# Arctos_65_V0.net
KiCad netlist of a schematic drawn in EAGLE
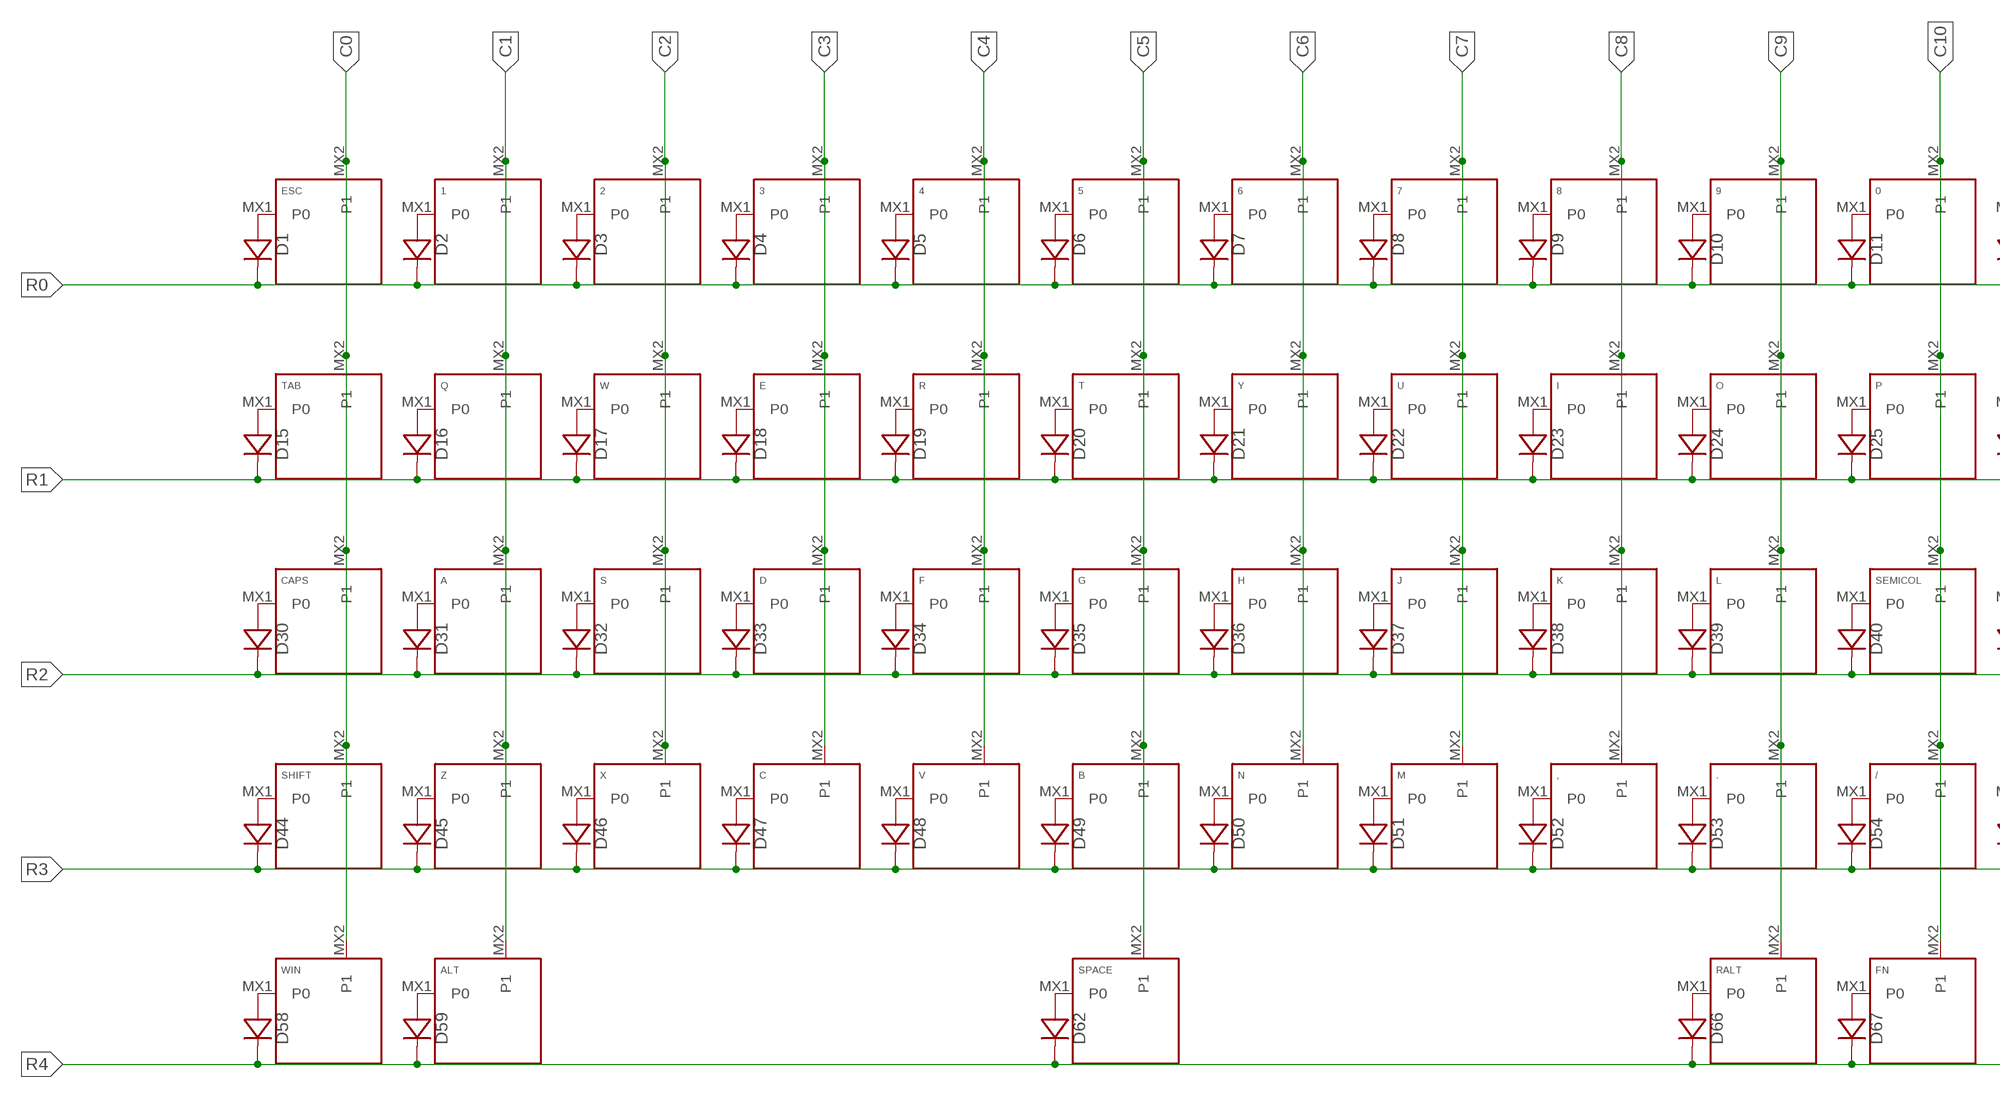
[diagram p0: schematic, sheet 1, part 1 of 2]
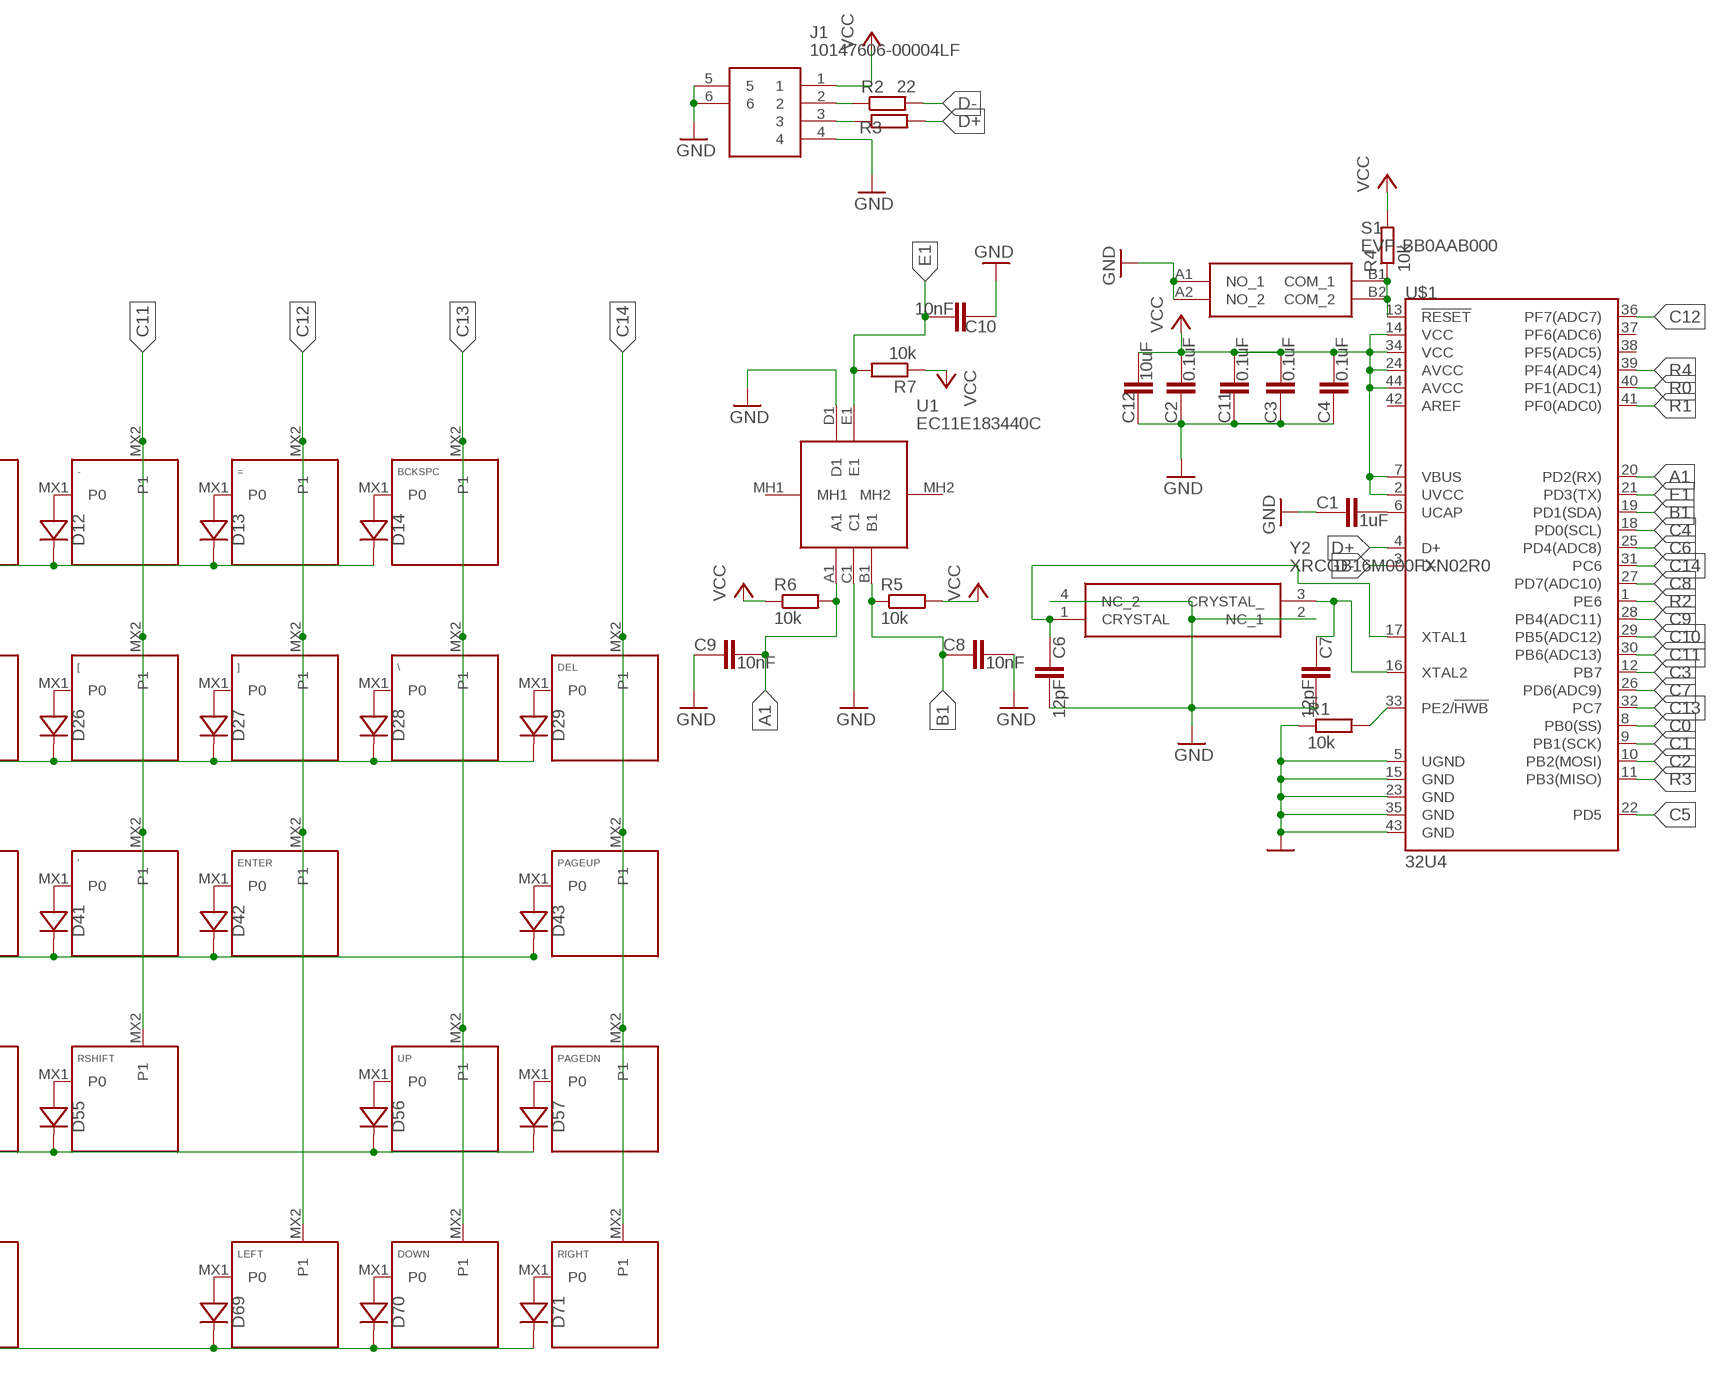
[diagram p1: schematic, sheet 1, part 2 of 2]

(export (version "E")
  (design (tool "Eeschema 10.0.6"))
  (components
    (comp (ref "'")
      (value "KEYSWITCH-PLAIN-MXHSPCB-1U")
      (footprint "eagle-import:MXHSPCB-1U")
      (libsource (lib "eagle-import") (part "KEYSWITCH-PLAIN-MXHSPCB-1U"))
    )
    (comp (ref ",")
      (value "KEYSWITCH-PLAIN-MXHSPCB-1U")
      (footprint "eagle-import:MXHSPCB-1U")
      (libsource (lib "eagle-import") (part "KEYSWITCH-PLAIN-MXHSPCB-1U"))
    )
    (comp (ref "-")
      (value "KEYSWITCH-PLAIN-MXHSPCB-1U")
      (footprint "eagle-import:MXHSPCB-1U")
      (libsource (lib "eagle-import") (part "KEYSWITCH-PLAIN-MXHSPCB-1U"))
    )
    (comp (ref ".")
      (value "KEYSWITCH-PLAIN-MXHSPCB-1U")
      (footprint "eagle-import:MXHSPCB-1U")
      (libsource (lib "eagle-import") (part "KEYSWITCH-PLAIN-MXHSPCB-1U"))
    )
    (comp (ref "/")
      (value "KEYSWITCH-PLAIN-MXHSPCB-1U")
      (footprint "eagle-import:MXHSPCB-1U")
      (libsource (lib "eagle-import") (part "KEYSWITCH-PLAIN-MXHSPCB-1U"))
    )
    (comp (ref "0")
      (value "KEYSWITCH-PLAIN-MXHSPCB-1U")
      (footprint "eagle-import:MXHSPCB-1U")
      (libsource (lib "eagle-import") (part "KEYSWITCH-PLAIN-MXHSPCB-1U"))
    )
    (comp (ref "1")
      (value "KEYSWITCH-PLAIN-MXHSPCB-1U")
      (footprint "eagle-import:MXHSPCB-1U")
      (libsource (lib "eagle-import") (part "KEYSWITCH-PLAIN-MXHSPCB-1U"))
    )
    (comp (ref "2")
      (value "KEYSWITCH-PLAIN-MXHSPCB-1U")
      (footprint "eagle-import:MXHSPCB-1U")
      (libsource (lib "eagle-import") (part "KEYSWITCH-PLAIN-MXHSPCB-1U"))
    )
    (comp (ref "3")
      (value "KEYSWITCH-PLAIN-MXHSPCB-1U")
      (footprint "eagle-import:MXHSPCB-1U")
      (libsource (lib "eagle-import") (part "KEYSWITCH-PLAIN-MXHSPCB-1U"))
    )
    (comp (ref "4")
      (value "KEYSWITCH-PLAIN-MXHSPCB-1U")
      (footprint "eagle-import:MXHSPCB-1U")
      (libsource (lib "eagle-import") (part "KEYSWITCH-PLAIN-MXHSPCB-1U"))
    )
    (comp (ref "5")
      (value "KEYSWITCH-PLAIN-MXHSPCB-1U")
      (footprint "eagle-import:MXHSPCB-1U")
      (libsource (lib "eagle-import") (part "KEYSWITCH-PLAIN-MXHSPCB-1U"))
    )
    (comp (ref "6")
      (value "KEYSWITCH-PLAIN-MXHSPCB-1U")
      (footprint "eagle-import:MXHSPCB-1U")
      (libsource (lib "eagle-import") (part "KEYSWITCH-PLAIN-MXHSPCB-1U"))
    )
    (comp (ref "7")
      (value "KEYSWITCH-PLAIN-MXHSPCB-1U")
      (footprint "eagle-import:MXHSPCB-1U")
      (libsource (lib "eagle-import") (part "KEYSWITCH-PLAIN-MXHSPCB-1U"))
    )
    (comp (ref "8")
      (value "KEYSWITCH-PLAIN-MXHSPCB-1U")
      (footprint "eagle-import:MXHSPCB-1U")
      (libsource (lib "eagle-import") (part "KEYSWITCH-PLAIN-MXHSPCB-1U"))
    )
    (comp (ref "9")
      (value "KEYSWITCH-PLAIN-MXHSPCB-1U")
      (footprint "eagle-import:MXHSPCB-1U")
      (libsource (lib "eagle-import") (part "KEYSWITCH-PLAIN-MXHSPCB-1U"))
    )
    (comp (ref "=")
      (value "KEYSWITCH-PLAIN-MXHSPCB-1U")
      (footprint "eagle-import:MXHSPCB-1U")
      (libsource (lib "eagle-import") (part "KEYSWITCH-PLAIN-MXHSPCB-1U"))
    )
    (comp (ref "A")
      (value "KEYSWITCH-PLAIN-MXHSPCB-1U")
      (footprint "eagle-import:MXHSPCB-1U")
      (libsource (lib "eagle-import") (part "KEYSWITCH-PLAIN-MXHSPCB-1U"))
    )
    (comp (ref "ALT")
      (value "KEYSWITCH-PLAIN-MXHSPCB-1U")
      (footprint "eagle-import:MXHSPCB-1U")
      (libsource (lib "eagle-import") (part "KEYSWITCH-PLAIN-MXHSPCB-1U"))
    )
    (comp (ref "B")
      (value "KEYSWITCH-PLAIN-MXHSPCB-1U")
      (footprint "eagle-import:MXHSPCB-1U")
      (libsource (lib "eagle-import") (part "KEYSWITCH-PLAIN-MXHSPCB-1U"))
    )
    (comp (ref "BCKSPC")
      (value "KEYSWITCH-PLAIN-MXHSPCB-2U")
      (footprint "eagle-import:MXHSPCB-2U")
      (libsource (lib "eagle-import") (part "KEYSWITCH-PLAIN-MXHSPCB-2U"))
    )
    (comp (ref "C")
      (value "KEYSWITCH-PLAIN-MXHSPCB-1U")
      (footprint "eagle-import:MXHSPCB-1U")
      (libsource (lib "eagle-import") (part "KEYSWITCH-PLAIN-MXHSPCB-1U"))
    )
    (comp (ref "C1")
      (value "1uF")
      (footprint "eagle-import:C0603")
      (libsource (lib "eagle-import") (part "CAPACITOR-0603"))
    )
    (comp (ref "C2")
      (value "0.1uF")
      (footprint "eagle-import:C0603")
      (libsource (lib "eagle-import") (part "CAPACITOR-0603"))
    )
    (comp (ref "C3")
      (value "0.1uF")
      (footprint "eagle-import:C0603")
      (libsource (lib "eagle-import") (part "CAPACITOR-0603"))
    )
    (comp (ref "C4")
      (value "0.1uF")
      (footprint "eagle-import:C0603")
      (libsource (lib "eagle-import") (part "CAPACITOR-0603"))
    )
    (comp (ref "C6")
      (value "12pF")
      (footprint "eagle-import:C0603")
      (libsource (lib "eagle-import") (part "CAPACITOR-0603"))
    )
    (comp (ref "C7")
      (value "12pF")
      (footprint "eagle-import:C0603")
      (libsource (lib "eagle-import") (part "CAPACITOR-0603"))
    )
    (comp (ref "C8")
      (value "10nF")
      (footprint "eagle-import:C0603")
      (libsource (lib "eagle-import") (part "CAPACITOR-0603"))
    )
    (comp (ref "C9")
      (value "10nF")
      (footprint "eagle-import:C0603")
      (libsource (lib "eagle-import") (part "CAPACITOR-0603"))
    )
    (comp (ref "C10")
      (value "10nF")
      (footprint "eagle-import:C0603")
      (libsource (lib "eagle-import") (part "CAPACITOR-0603"))
    )
    (comp (ref "C11")
      (value "0.1uF")
      (footprint "eagle-import:C0603")
      (libsource (lib "eagle-import") (part "CAPACITOR-0603"))
    )
    (comp (ref "C12")
      (value "10uF")
      (footprint "eagle-import:C0603")
      (libsource (lib "eagle-import") (part "CAPACITOR-0603"))
    )
    (comp (ref "CAPS")
      (value "KEYSWITCH-PLAIN-MXHSPCB-1U")
      (footprint "eagle-import:MXHSPCB-1U")
      (libsource (lib "eagle-import") (part "KEYSWITCH-PLAIN-MXHSPCB-1U"))
    )
    (comp (ref "D")
      (value "KEYSWITCH-PLAIN-MXHSPCB-1U")
      (footprint "eagle-import:MXHSPCB-1U")
      (libsource (lib "eagle-import") (part "KEYSWITCH-PLAIN-MXHSPCB-1U"))
    )
    (comp (ref "D1")
      (value "DIODE-SOD-123")
      (footprint "eagle-import:SOD-123")
      (libsource (lib "eagle-import") (part "DIODE-SOD-123"))
    )
    (comp (ref "D2")
      (value "DIODE-SOD-123")
      (footprint "eagle-import:SOD-123")
      (libsource (lib "eagle-import") (part "DIODE-SOD-123"))
    )
    (comp (ref "D3")
      (value "DIODE-SOD-123")
      (footprint "eagle-import:SOD-123")
      (libsource (lib "eagle-import") (part "DIODE-SOD-123"))
    )
    (comp (ref "D4")
      (value "DIODE-SOD-123")
      (footprint "eagle-import:SOD-123")
      (libsource (lib "eagle-import") (part "DIODE-SOD-123"))
    )
    (comp (ref "D5")
      (value "DIODE-SOD-123")
      (footprint "eagle-import:SOD-123")
      (libsource (lib "eagle-import") (part "DIODE-SOD-123"))
    )
    (comp (ref "D6")
      (value "DIODE-SOD-123")
      (footprint "eagle-import:SOD-123")
      (libsource (lib "eagle-import") (part "DIODE-SOD-123"))
    )
    (comp (ref "D7")
      (value "DIODE-SOD-123")
      (footprint "eagle-import:SOD-123")
      (libsource (lib "eagle-import") (part "DIODE-SOD-123"))
    )
    (comp (ref "D8")
      (value "DIODE-SOD-123")
      (footprint "eagle-import:SOD-123")
      (libsource (lib "eagle-import") (part "DIODE-SOD-123"))
    )
    (comp (ref "D9")
      (value "DIODE-SOD-123")
      (footprint "eagle-import:SOD-123")
      (libsource (lib "eagle-import") (part "DIODE-SOD-123"))
    )
    (comp (ref "D10")
      (value "DIODE-SOD-123")
      (footprint "eagle-import:SOD-123")
      (libsource (lib "eagle-import") (part "DIODE-SOD-123"))
    )
    (comp (ref "D11")
      (value "DIODE-SOD-123")
      (footprint "eagle-import:SOD-123")
      (libsource (lib "eagle-import") (part "DIODE-SOD-123"))
    )
    (comp (ref "D12")
      (value "DIODE-SOD-123")
      (footprint "eagle-import:SOD-123")
      (libsource (lib "eagle-import") (part "DIODE-SOD-123"))
    )
    (comp (ref "D13")
      (value "DIODE-SOD-123")
      (footprint "eagle-import:SOD-123")
      (libsource (lib "eagle-import") (part "DIODE-SOD-123"))
    )
    (comp (ref "D14")
      (value "DIODE-SOD-123")
      (footprint "eagle-import:SOD-123")
      (libsource (lib "eagle-import") (part "DIODE-SOD-123"))
    )
    (comp (ref "D15")
      (value "DIODE-SOD-123")
      (footprint "eagle-import:SOD-123")
      (libsource (lib "eagle-import") (part "DIODE-SOD-123"))
    )
    (comp (ref "D16")
      (value "DIODE-SOD-123")
      (footprint "eagle-import:SOD-123")
      (libsource (lib "eagle-import") (part "DIODE-SOD-123"))
    )
    (comp (ref "D17")
      (value "DIODE-SOD-123")
      (footprint "eagle-import:SOD-123")
      (libsource (lib "eagle-import") (part "DIODE-SOD-123"))
    )
    (comp (ref "D18")
      (value "DIODE-SOD-123")
      (footprint "eagle-import:SOD-123")
      (libsource (lib "eagle-import") (part "DIODE-SOD-123"))
    )
    (comp (ref "D19")
      (value "DIODE-SOD-123")
      (footprint "eagle-import:SOD-123")
      (libsource (lib "eagle-import") (part "DIODE-SOD-123"))
    )
    (comp (ref "D20")
      (value "DIODE-SOD-123")
      (footprint "eagle-import:SOD-123")
      (libsource (lib "eagle-import") (part "DIODE-SOD-123"))
    )
    (comp (ref "D21")
      (value "DIODE-SOD-123")
      (footprint "eagle-import:SOD-123")
      (libsource (lib "eagle-import") (part "DIODE-SOD-123"))
    )
    (comp (ref "D22")
      (value "DIODE-SOD-123")
      (footprint "eagle-import:SOD-123")
      (libsource (lib "eagle-import") (part "DIODE-SOD-123"))
    )
    (comp (ref "D23")
      (value "DIODE-SOD-123")
      (footprint "eagle-import:SOD-123")
      (libsource (lib "eagle-import") (part "DIODE-SOD-123"))
    )
    (comp (ref "D24")
      (value "DIODE-SOD-123")
      (footprint "eagle-import:SOD-123")
      (libsource (lib "eagle-import") (part "DIODE-SOD-123"))
    )
    (comp (ref "D25")
      (value "DIODE-SOD-123")
      (footprint "eagle-import:SOD-123")
      (libsource (lib "eagle-import") (part "DIODE-SOD-123"))
    )
    (comp (ref "D26")
      (value "DIODE-SOD-123")
      (footprint "eagle-import:SOD-123")
      (libsource (lib "eagle-import") (part "DIODE-SOD-123"))
    )
    (comp (ref "D27")
      (value "DIODE-SOD-123")
      (footprint "eagle-import:SOD-123")
      (libsource (lib "eagle-import") (part "DIODE-SOD-123"))
    )
    (comp (ref "D28")
      (value "DIODE-SOD-123")
      (footprint "eagle-import:SOD-123")
      (libsource (lib "eagle-import") (part "DIODE-SOD-123"))
    )
    (comp (ref "D29")
      (value "DIODE-SOD-123")
      (footprint "eagle-import:SOD-123")
      (libsource (lib "eagle-import") (part "DIODE-SOD-123"))
    )
    (comp (ref "D30")
      (value "DIODE-SOD-123")
      (footprint "eagle-import:SOD-123")
      (libsource (lib "eagle-import") (part "DIODE-SOD-123"))
    )
    (comp (ref "D31")
      (value "DIODE-SOD-123")
      (footprint "eagle-import:SOD-123")
      (libsource (lib "eagle-import") (part "DIODE-SOD-123"))
    )
    (comp (ref "D32")
      (value "DIODE-SOD-123")
      (footprint "eagle-import:SOD-123")
      (libsource (lib "eagle-import") (part "DIODE-SOD-123"))
    )
    (comp (ref "D33")
      (value "DIODE-SOD-123")
      (footprint "eagle-import:SOD-123")
      (libsource (lib "eagle-import") (part "DIODE-SOD-123"))
    )
    (comp (ref "D34")
      (value "DIODE-SOD-123")
      (footprint "eagle-import:SOD-123")
      (libsource (lib "eagle-import") (part "DIODE-SOD-123"))
    )
    (comp (ref "D35")
      (value "DIODE-SOD-123")
      (footprint "eagle-import:SOD-123")
      (libsource (lib "eagle-import") (part "DIODE-SOD-123"))
    )
    (comp (ref "D36")
      (value "DIODE-SOD-123")
      (footprint "eagle-import:SOD-123")
      (libsource (lib "eagle-import") (part "DIODE-SOD-123"))
    )
    (comp (ref "D37")
      (value "DIODE-SOD-123")
      (footprint "eagle-import:SOD-123")
      (libsource (lib "eagle-import") (part "DIODE-SOD-123"))
    )
    (comp (ref "D38")
      (value "DIODE-SOD-123")
      (footprint "eagle-import:SOD-123")
      (libsource (lib "eagle-import") (part "DIODE-SOD-123"))
    )
    (comp (ref "D39")
      (value "DIODE-SOD-123")
      (footprint "eagle-import:SOD-123")
      (libsource (lib "eagle-import") (part "DIODE-SOD-123"))
    )
    (comp (ref "D40")
      (value "DIODE-SOD-123")
      (footprint "eagle-import:SOD-123")
      (libsource (lib "eagle-import") (part "DIODE-SOD-123"))
    )
    (comp (ref "D41")
      (value "DIODE-SOD-123")
      (footprint "eagle-import:SOD-123")
      (libsource (lib "eagle-import") (part "DIODE-SOD-123"))
    )
    (comp (ref "D42")
      (value "DIODE-SOD-123")
      (footprint "eagle-import:SOD-123")
      (libsource (lib "eagle-import") (part "DIODE-SOD-123"))
    )
    (comp (ref "D43")
      (value "DIODE-SOD-123")
      (footprint "eagle-import:SOD-123")
      (libsource (lib "eagle-import") (part "DIODE-SOD-123"))
    )
    (comp (ref "D44")
      (value "DIODE-SOD-123")
      (footprint "eagle-import:SOD-123")
      (libsource (lib "eagle-import") (part "DIODE-SOD-123"))
    )
    (comp (ref "D45")
      (value "DIODE-SOD-123")
      (footprint "eagle-import:SOD-123")
      (libsource (lib "eagle-import") (part "DIODE-SOD-123"))
    )
    (comp (ref "D46")
      (value "DIODE-SOD-123")
      (footprint "eagle-import:SOD-123")
      (libsource (lib "eagle-import") (part "DIODE-SOD-123"))
    )
    (comp (ref "D47")
      (value "DIODE-SOD-123")
      (footprint "eagle-import:SOD-123")
      (libsource (lib "eagle-import") (part "DIODE-SOD-123"))
    )
    (comp (ref "D48")
      (value "DIODE-SOD-123")
      (footprint "eagle-import:SOD-123")
      (libsource (lib "eagle-import") (part "DIODE-SOD-123"))
    )
    (comp (ref "D49")
      (value "DIODE-SOD-123")
      (footprint "eagle-import:SOD-123")
      (libsource (lib "eagle-import") (part "DIODE-SOD-123"))
    )
    (comp (ref "D50")
      (value "DIODE-SOD-123")
      (footprint "eagle-import:SOD-123")
      (libsource (lib "eagle-import") (part "DIODE-SOD-123"))
    )
    (comp (ref "D51")
      (value "DIODE-SOD-123")
      (footprint "eagle-import:SOD-123")
      (libsource (lib "eagle-import") (part "DIODE-SOD-123"))
    )
    (comp (ref "D52")
      (value "DIODE-SOD-123")
      (footprint "eagle-import:SOD-123")
      (libsource (lib "eagle-import") (part "DIODE-SOD-123"))
    )
    (comp (ref "D53")
      (value "DIODE-SOD-123")
      (footprint "eagle-import:SOD-123")
      (libsource (lib "eagle-import") (part "DIODE-SOD-123"))
    )
    (comp (ref "D54")
      (value "DIODE-SOD-123")
      (footprint "eagle-import:SOD-123")
      (libsource (lib "eagle-import") (part "DIODE-SOD-123"))
    )
    (comp (ref "D55")
      (value "DIODE-SOD-123")
      (footprint "eagle-import:SOD-123")
      (libsource (lib "eagle-import") (part "DIODE-SOD-123"))
    )
    (comp (ref "D56")
      (value "DIODE-SOD-123")
      (footprint "eagle-import:SOD-123")
      (libsource (lib "eagle-import") (part "DIODE-SOD-123"))
    )
    (comp (ref "D57")
      (value "DIODE-SOD-123")
      (footprint "eagle-import:SOD-123")
      (libsource (lib "eagle-import") (part "DIODE-SOD-123"))
    )
    (comp (ref "D58")
      (value "DIODE-SOD-123")
      (footprint "eagle-import:SOD-123")
      (libsource (lib "eagle-import") (part "DIODE-SOD-123"))
    )
    (comp (ref "D59")
      (value "DIODE-SOD-123")
      (footprint "eagle-import:SOD-123")
      (libsource (lib "eagle-import") (part "DIODE-SOD-123"))
    )
    (comp (ref "D62")
      (value "DIODE-SOD-123")
      (footprint "eagle-import:SOD-123")
      (libsource (lib "eagle-import") (part "DIODE-SOD-123"))
    )
    (comp (ref "D66")
      (value "DIODE-SOD-123")
      (footprint "eagle-import:SOD-123")
      (libsource (lib "eagle-import") (part "DIODE-SOD-123"))
    )
    (comp (ref "D67")
      (value "DIODE-SOD-123")
      (footprint "eagle-import:SOD-123")
      (libsource (lib "eagle-import") (part "DIODE-SOD-123"))
    )
    (comp (ref "D69")
      (value "DIODE-SOD-123")
      (footprint "eagle-import:SOD-123")
      (libsource (lib "eagle-import") (part "DIODE-SOD-123"))
    )
    (comp (ref "D70")
      (value "DIODE-SOD-123")
      (footprint "eagle-import:SOD-123")
      (libsource (lib "eagle-import") (part "DIODE-SOD-123"))
    )
    (comp (ref "D71")
      (value "DIODE-SOD-123")
      (footprint "eagle-import:SOD-123")
      (libsource (lib "eagle-import") (part "DIODE-SOD-123"))
    )
    (comp (ref "DEL")
      (value "KEYSWITCH-PLAIN-MXHSPCB-1U")
      (footprint "eagle-import:MXHSPCB-1U")
      (libsource (lib "eagle-import") (part "KEYSWITCH-PLAIN-MXHSPCB-1U"))
    )
    (comp (ref "DOWN")
      (value "KEYSWITCH-PLAIN-MXHSPCB-1U")
      (footprint "eagle-import:MXHSPCB-1U")
      (libsource (lib "eagle-import") (part "KEYSWITCH-PLAIN-MXHSPCB-1U"))
    )
    (comp (ref "E")
      (value "KEYSWITCH-PLAIN-MXHSPCB-1U")
      (footprint "eagle-import:MXHSPCB-1U")
      (libsource (lib "eagle-import") (part "KEYSWITCH-PLAIN-MXHSPCB-1U"))
    )
    (comp (ref "ENTER")
      (value "KEYSWITCH-PLAIN-MXHSPCB-2U")
      (footprint "eagle-import:MXHSPCB-2U")
      (libsource (lib "eagle-import") (part "KEYSWITCH-PLAIN-MXHSPCB-2U"))
    )
    (comp (ref "ESC")
      (value "KEYSWITCH-PLAIN-MXHSPCB-1U")
      (footprint "eagle-import:MXHSPCB-1U")
      (libsource (lib "eagle-import") (part "KEYSWITCH-PLAIN-MXHSPCB-1U"))
    )
    (comp (ref "F")
      (value "KEYSWITCH-PLAIN-MXHSPCB-1U")
      (footprint "eagle-import:MXHSPCB-1U")
      (libsource (lib "eagle-import") (part "KEYSWITCH-PLAIN-MXHSPCB-1U"))
    )
    (comp (ref "FN")
      (value "KEYSWITCH-PLAIN-MXHSPCB-1U")
      (footprint "eagle-import:MXHSPCB-1U")
      (libsource (lib "eagle-import") (part "KEYSWITCH-PLAIN-MXHSPCB-1U"))
    )
    (comp (ref "G")
      (value "KEYSWITCH-PLAIN-MXHSPCB-1U")
      (footprint "eagle-import:MXHSPCB-1U")
      (libsource (lib "eagle-import") (part "KEYSWITCH-PLAIN-MXHSPCB-1U"))
    )
    (comp (ref "H")
      (value "KEYSWITCH-PLAIN-MXHSPCB-1U")
      (footprint "eagle-import:MXHSPCB-1U")
      (libsource (lib "eagle-import") (part "KEYSWITCH-PLAIN-MXHSPCB-1U"))
    )
    (comp (ref "I")
      (value "KEYSWITCH-PLAIN-MXHSPCB-1U")
      (footprint "eagle-import:MXHSPCB-1U")
      (libsource (lib "eagle-import") (part "KEYSWITCH-PLAIN-MXHSPCB-1U"))
    )
    (comp (ref "J")
      (value "KEYSWITCH-PLAIN-MXHSPCB-1U")
      (footprint "eagle-import:MXHSPCB-1U")
      (libsource (lib "eagle-import") (part "KEYSWITCH-PLAIN-MXHSPCB-1U"))
    )
    (comp (ref "J1")
      (value "10147606-00004LF")
      (footprint "eagle-import:1014760600004LF")
      (fields (field (name "MOUSER_PART_NUMBER") "649-10147606-00004LF"))
      (libsource (lib "eagle-import") (part "10147606-00004LF"))
    )
    (comp (ref "K")
      (value "KEYSWITCH-PLAIN-MXHSPCB-1U")
      (footprint "eagle-import:MXHSPCB-1U")
      (libsource (lib "eagle-import") (part "KEYSWITCH-PLAIN-MXHSPCB-1U"))
    )
    (comp (ref "L")
      (value "KEYSWITCH-PLAIN-MXHSPCB-1U")
      (footprint "eagle-import:MXHSPCB-1U")
      (libsource (lib "eagle-import") (part "KEYSWITCH-PLAIN-MXHSPCB-1U"))
    )
    (comp (ref "LEFT")
      (value "KEYSWITCH-PLAIN-MXHSPCB-1U")
      (footprint "eagle-import:MXHSPCB-1U")
      (libsource (lib "eagle-import") (part "KEYSWITCH-PLAIN-MXHSPCB-1U"))
    )
    (comp (ref "M")
      (value "KEYSWITCH-PLAIN-MXHSPCB-1U")
      (footprint "eagle-import:MXHSPCB-1U")
      (libsource (lib "eagle-import") (part "KEYSWITCH-PLAIN-MXHSPCB-1U"))
    )
    (comp (ref "N")
      (value "KEYSWITCH-PLAIN-MXHSPCB-1U")
      (footprint "eagle-import:MXHSPCB-1U")
      (libsource (lib "eagle-import") (part "KEYSWITCH-PLAIN-MXHSPCB-1U"))
    )
    (comp (ref "O")
      (value "KEYSWITCH-PLAIN-MXHSPCB-1U")
      (footprint "eagle-import:MXHSPCB-1U")
      (libsource (lib "eagle-import") (part "KEYSWITCH-PLAIN-MXHSPCB-1U"))
    )
    (comp (ref "P")
      (value "KEYSWITCH-PLAIN-MXHSPCB-1U")
      (footprint "eagle-import:MXHSPCB-1U")
      (libsource (lib "eagle-import") (part "KEYSWITCH-PLAIN-MXHSPCB-1U"))
    )
    (comp (ref "PAGEDN")
      (value "KEYSWITCH-PLAIN-MXHSPCB-1U")
      (footprint "eagle-import:MXHSPCB-1U")
      (libsource (lib "eagle-import") (part "KEYSWITCH-PLAIN-MXHSPCB-1U"))
    )
    (comp (ref "PAGEUP")
      (value "KEYSWITCH-PLAIN-MXHSPCB-1U")
      (footprint "eagle-import:MXHSPCB-1U")
      (libsource (lib "eagle-import") (part "KEYSWITCH-PLAIN-MXHSPCB-1U"))
    )
    (comp (ref "Q")
      (value "KEYSWITCH-PLAIN-MXHSPCB-1U")
      (footprint "eagle-import:MXHSPCB-1U")
      (libsource (lib "eagle-import") (part "KEYSWITCH-PLAIN-MXHSPCB-1U"))
    )
    (comp (ref "R")
      (value "KEYSWITCH-PLAIN-MXHSPCB-1U")
      (footprint "eagle-import:MXHSPCB-1U")
      (libsource (lib "eagle-import") (part "KEYSWITCH-PLAIN-MXHSPCB-1U"))
    )
    (comp (ref "R1")
      (value "10k")
      (footprint "eagle-import:R0603")
      (libsource (lib "eagle-import") (part "RESISTOR-0603"))
    )
    (comp (ref "R2")
      (value "22")
      (footprint "eagle-import:R0603")
      (libsource (lib "eagle-import") (part "RESISTOR-0603"))
    )
    (comp (ref "R3")
      (value "22")
      (footprint "eagle-import:R0603")
      (libsource (lib "eagle-import") (part "RESISTOR-0603"))
    )
    (comp (ref "R4")
      (value "10k")
      (footprint "eagle-import:R0603")
      (libsource (lib "eagle-import") (part "RESISTOR-0603"))
    )
    (comp (ref "R5")
      (value "10k")
      (footprint "eagle-import:R0603")
      (libsource (lib "eagle-import") (part "RESISTOR-0603"))
    )
    (comp (ref "R6")
      (value "10k")
      (footprint "eagle-import:R0603")
      (libsource (lib "eagle-import") (part "RESISTOR-0603"))
    )
    (comp (ref "R7")
      (value "10k")
      (footprint "eagle-import:R0603")
      (libsource (lib "eagle-import") (part "RESISTOR-0603"))
    )
    (comp (ref "RALT")
      (value "KEYSWITCH-PLAIN-MXHSPCB-1U")
      (footprint "eagle-import:MXHSPCB-1U")
      (libsource (lib "eagle-import") (part "KEYSWITCH-PLAIN-MXHSPCB-1U"))
    )
    (comp (ref "RIGHT")
      (value "KEYSWITCH-PLAIN-MXHSPCB-1U")
      (footprint "eagle-import:MXHSPCB-1U")
      (libsource (lib "eagle-import") (part "KEYSWITCH-PLAIN-MXHSPCB-1U"))
    )
    (comp (ref "RSHIFT")
      (value "KEYSWITCH-PLAIN-MXHSPCB-1U")
      (footprint "eagle-import:MXHSPCB-1U")
      (libsource (lib "eagle-import") (part "KEYSWITCH-PLAIN-MXHSPCB-1U"))
    )
    (comp (ref "S")
      (value "KEYSWITCH-PLAIN-MXHSPCB-1U")
      (footprint "eagle-import:MXHSPCB-1U")
      (libsource (lib "eagle-import") (part "KEYSWITCH-PLAIN-MXHSPCB-1U"))
    )
    (comp (ref "S1")
      (value "EVP-BB0AAB000")
      (footprint "eagle-import:EVPBB0AAB000")
      (fields (field (name "MOUSER_PART_NUMBER") "667-EVP-BB0AAB000"))
      (libsource (lib "eagle-import") (part "EVP-BB0AAB000"))
    )
    (comp (ref "SEMICOL")
      (value "KEYSWITCH-PLAIN-MXHSPCB-1U")
      (footprint "eagle-import:MXHSPCB-1U")
      (libsource (lib "eagle-import") (part "KEYSWITCH-PLAIN-MXHSPCB-1U"))
    )
    (comp (ref "SHIFT")
      (value "KEYSWITCH-PLAIN-MXHSPCB-2U")
      (footprint "eagle-import:MXHSPCB-2U")
      (libsource (lib "eagle-import") (part "KEYSWITCH-PLAIN-MXHSPCB-2U"))
    )
    (comp (ref "SPACE")
      (value "KEYSWITCH-PLAIN-MXHSPCB-7U-FLIPPED")
      (footprint "eagle-import:MXHSPCB-7U-FLIPPED")
      (libsource (lib "eagle-import") (part "KEYSWITCH-PLAIN-MXHSPCB-7U-FLIPPED"))
    )
    (comp (ref "T")
      (value "KEYSWITCH-PLAIN-MXHSPCB-1U")
      (footprint "eagle-import:MXHSPCB-1U")
      (libsource (lib "eagle-import") (part "KEYSWITCH-PLAIN-MXHSPCB-1U"))
    )
    (comp (ref "TAB")
      (value "KEYSWITCH-PLAIN-MXHSPCB-1U")
      (footprint "eagle-import:MXHSPCB-1U")
      (libsource (lib "eagle-import") (part "KEYSWITCH-PLAIN-MXHSPCB-1U"))
    )
    (comp (ref "U")
      (value "KEYSWITCH-PLAIN-MXHSPCB-1U")
      (footprint "eagle-import:MXHSPCB-1U")
      (libsource (lib "eagle-import") (part "KEYSWITCH-PLAIN-MXHSPCB-1U"))
    )
    (comp (ref "U$1")
      (value "32U4")
      (footprint "eagle-import:TQFP44")
      (libsource (lib "eagle-import") (part "ATMEGA32U4TQFP-44"))
    )
    (comp (ref "U1")
      (value "EC11E183440C")
      (footprint "eagle-import:EC11E183440C")
      (fields (field (name "MOUSER_PART_NUMBER") "688-EC11E183440C"))
      (libsource (lib "eagle-import") (part "EC11E183440C"))
    )
    (comp (ref "UP")
      (value "KEYSWITCH-PLAIN-MXHSPCB-1U")
      (footprint "eagle-import:MXHSPCB-1U")
      (libsource (lib "eagle-import") (part "KEYSWITCH-PLAIN-MXHSPCB-1U"))
    )
    (comp (ref "V")
      (value "KEYSWITCH-PLAIN-MXHSPCB-1U")
      (footprint "eagle-import:MXHSPCB-1U")
      (libsource (lib "eagle-import") (part "KEYSWITCH-PLAIN-MXHSPCB-1U"))
    )
    (comp (ref "W")
      (value "KEYSWITCH-PLAIN-MXHSPCB-1U")
      (footprint "eagle-import:MXHSPCB-1U")
      (libsource (lib "eagle-import") (part "KEYSWITCH-PLAIN-MXHSPCB-1U"))
    )
    (comp (ref "WIN")
      (value "KEYSWITCH-PLAIN-MXHSPCB-1U")
      (footprint "eagle-import:MXHSPCB-1U")
      (libsource (lib "eagle-import") (part "KEYSWITCH-PLAIN-MXHSPCB-1U"))
    )
    (comp (ref "X")
      (value "KEYSWITCH-PLAIN-MXHSPCB-1U")
      (footprint "eagle-import:MXHSPCB-1U")
      (libsource (lib "eagle-import") (part "KEYSWITCH-PLAIN-MXHSPCB-1U"))
    )
    (comp (ref "Y")
      (value "KEYSWITCH-PLAIN-MXHSPCB-1U")
      (footprint "eagle-import:MXHSPCB-1U")
      (libsource (lib "eagle-import") (part "KEYSWITCH-PLAIN-MXHSPCB-1U"))
    )
    (comp (ref "Y2")
      (value "XRCGB16M000FXN02R0")
      (footprint "eagle-import:XRCGB16M000FXN02R0")
      (fields (field (name "MOUSER_PART_NUMBER") "81-XRCGB16M000FXN02R"))
      (libsource (lib "eagle-import") (part "XRCGB16M000FXN02R0"))
    )
    (comp (ref "Z")
      (value "KEYSWITCH-PLAIN-MXHSPCB-1U")
      (footprint "eagle-import:MXHSPCB-1U")
      (libsource (lib "eagle-import") (part "KEYSWITCH-PLAIN-MXHSPCB-1U"))
    )
    (comp (ref "[")
      (value "KEYSWITCH-PLAIN-MXHSPCB-1U")
      (footprint "eagle-import:MXHSPCB-1U")
      (libsource (lib "eagle-import") (part "KEYSWITCH-PLAIN-MXHSPCB-1U"))
    )
    (comp (ref "\\")
      (value "KEYSWITCH-PLAIN-MXHSPCB-1U")
      (footprint "eagle-import:MXHSPCB-1U")
      (libsource (lib "eagle-import") (part "KEYSWITCH-PLAIN-MXHSPCB-1U"))
    )
    (comp (ref "]")
      (value "KEYSWITCH-PLAIN-MXHSPCB-1U")
      (footprint "eagle-import:MXHSPCB-1U")
      (libsource (lib "eagle-import") (part "KEYSWITCH-PLAIN-MXHSPCB-1U"))
    )
  )
  (nets
    (net (code "1") (name "A1") (class "Default")
      (node (ref "C9") (pin "2") (pinfunction "2_2") (pintype "passive"))
      (node (ref "R6") (pin "2") (pinfunction "2_2") (pintype "passive"))
      (node (ref "U$1") (pin "20") (pinfunction "PD2(RX)_20") (pintype "bidirectional"))
      (node (ref "U1") (pin "A1") (pinfunction "A1_A1") (pintype "bidirectional"))
    )
    (net (code "2") (name "B1") (class "Default")
      (node (ref "C8") (pin "1") (pinfunction "1_1") (pintype "passive"))
      (node (ref "R5") (pin "1") (pinfunction "1_1") (pintype "passive"))
      (node (ref "U$1") (pin "19") (pinfunction "PD1(SDA)_19") (pintype "bidirectional"))
      (node (ref "U1") (pin "B1") (pinfunction "B1_B1") (pintype "bidirectional"))
    )
    (net (code "3") (name "C0") (class "Default")
      (node (ref "CAPS") (pin "MX2") (pinfunction "P1_MX2") (pintype "bidirectional"))
      (node (ref "ESC") (pin "MX2") (pinfunction "P1_MX2") (pintype "bidirectional"))
      (node (ref "SHIFT") (pin "MX2") (pinfunction "P1_MX2") (pintype "bidirectional"))
      (node (ref "TAB") (pin "MX2") (pinfunction "P1_MX2") (pintype "bidirectional"))
      (node (ref "U$1") (pin "8") (pinfunction "PB0(SS)_8") (pintype "bidirectional"))
      (node (ref "WIN") (pin "MX2") (pinfunction "P1_MX2") (pintype "bidirectional"))
    )
    (net (code "4") (name "C1") (class "Default")
      (node (ref "1") (pin "MX2") (pinfunction "P1_MX2") (pintype "bidirectional"))
      (node (ref "A") (pin "MX2") (pinfunction "P1_MX2") (pintype "bidirectional"))
      (node (ref "ALT") (pin "MX2") (pinfunction "P1_MX2") (pintype "bidirectional"))
      (node (ref "Q") (pin "MX2") (pinfunction "P1_MX2") (pintype "bidirectional"))
      (node (ref "U$1") (pin "9") (pinfunction "PB1(SCK)_9") (pintype "bidirectional"))
      (node (ref "Z") (pin "MX2") (pinfunction "P1_MX2") (pintype "bidirectional"))
    )
    (net (code "5") (name "C2") (class "Default")
      (node (ref "2") (pin "MX2") (pinfunction "P1_MX2") (pintype "bidirectional"))
      (node (ref "S") (pin "MX2") (pinfunction "P1_MX2") (pintype "bidirectional"))
      (node (ref "U$1") (pin "10") (pinfunction "PB2(MOSI)_10") (pintype "bidirectional"))
      (node (ref "W") (pin "MX2") (pinfunction "P1_MX2") (pintype "bidirectional"))
      (node (ref "X") (pin "MX2") (pinfunction "P1_MX2") (pintype "bidirectional"))
    )
    (net (code "6") (name "C3") (class "Default")
      (node (ref "3") (pin "MX2") (pinfunction "P1_MX2") (pintype "bidirectional"))
      (node (ref "C") (pin "MX2") (pinfunction "P1_MX2") (pintype "bidirectional"))
      (node (ref "D") (pin "MX2") (pinfunction "P1_MX2") (pintype "bidirectional"))
      (node (ref "E") (pin "MX2") (pinfunction "P1_MX2") (pintype "bidirectional"))
      (node (ref "U$1") (pin "12") (pinfunction "PB7_12") (pintype "bidirectional"))
    )
    (net (code "7") (name "C4") (class "Default")
      (node (ref "4") (pin "MX2") (pinfunction "P1_MX2") (pintype "bidirectional"))
      (node (ref "F") (pin "MX2") (pinfunction "P1_MX2") (pintype "bidirectional"))
      (node (ref "R") (pin "MX2") (pinfunction "P1_MX2") (pintype "bidirectional"))
      (node (ref "U$1") (pin "18") (pinfunction "PD0(SCL)_18") (pintype "bidirectional"))
      (node (ref "V") (pin "MX2") (pinfunction "P1_MX2") (pintype "bidirectional"))
    )
    (net (code "8") (name "C5") (class "Default")
      (node (ref "5") (pin "MX2") (pinfunction "P1_MX2") (pintype "bidirectional"))
      (node (ref "B") (pin "MX2") (pinfunction "P1_MX2") (pintype "bidirectional"))
      (node (ref "G") (pin "MX2") (pinfunction "P1_MX2") (pintype "bidirectional"))
      (node (ref "SPACE") (pin "MX2") (pinfunction "P1_MX2") (pintype "bidirectional"))
      (node (ref "T") (pin "MX2") (pinfunction "P1_MX2") (pintype "bidirectional"))
      (node (ref "U$1") (pin "22") (pinfunction "PD5_22") (pintype "bidirectional"))
    )
    (net (code "9") (name "C6") (class "Default")
      (node (ref "6") (pin "MX2") (pinfunction "P1_MX2") (pintype "bidirectional"))
      (node (ref "H") (pin "MX2") (pinfunction "P1_MX2") (pintype "bidirectional"))
      (node (ref "N") (pin "MX2") (pinfunction "P1_MX2") (pintype "bidirectional"))
      (node (ref "U$1") (pin "25") (pinfunction "PD4(ADC8)_25") (pintype "bidirectional"))
      (node (ref "Y") (pin "MX2") (pinfunction "P1_MX2") (pintype "bidirectional"))
    )
    (net (code "10") (name "C7") (class "Default")
      (node (ref "7") (pin "MX2") (pinfunction "P1_MX2") (pintype "bidirectional"))
      (node (ref "J") (pin "MX2") (pinfunction "P1_MX2") (pintype "bidirectional"))
      (node (ref "M") (pin "MX2") (pinfunction "P1_MX2") (pintype "bidirectional"))
      (node (ref "U") (pin "MX2") (pinfunction "P1_MX2") (pintype "bidirectional"))
      (node (ref "U$1") (pin "26") (pinfunction "PD6(ADC9)_26") (pintype "bidirectional"))
    )
    (net (code "11") (name "C8") (class "Default")
      (node (ref ",") (pin "MX2") (pinfunction "P1_MX2") (pintype "bidirectional"))
      (node (ref "8") (pin "MX2") (pinfunction "P1_MX2") (pintype "bidirectional"))
      (node (ref "I") (pin "MX2") (pinfunction "P1_MX2") (pintype "bidirectional"))
      (node (ref "K") (pin "MX2") (pinfunction "P1_MX2") (pintype "bidirectional"))
      (node (ref "U$1") (pin "27") (pinfunction "PD7(ADC10)_27") (pintype "bidirectional"))
    )
    (net (code "12") (name "C9") (class "Default")
      (node (ref ".") (pin "MX2") (pinfunction "P1_MX2") (pintype "bidirectional"))
      (node (ref "9") (pin "MX2") (pinfunction "P1_MX2") (pintype "bidirectional"))
      (node (ref "L") (pin "MX2") (pinfunction "P1_MX2") (pintype "bidirectional"))
      (node (ref "O") (pin "MX2") (pinfunction "P1_MX2") (pintype "bidirectional"))
      (node (ref "RALT") (pin "MX2") (pinfunction "P1_MX2") (pintype "bidirectional"))
      (node (ref "U$1") (pin "28") (pinfunction "PB4(ADC11)_28") (pintype "bidirectional"))
    )
    (net (code "13") (name "C10") (class "Default")
      (node (ref "/") (pin "MX2") (pinfunction "P1_MX2") (pintype "bidirectional"))
      (node (ref "0") (pin "MX2") (pinfunction "P1_MX2") (pintype "bidirectional"))
      (node (ref "FN") (pin "MX2") (pinfunction "P1_MX2") (pintype "bidirectional"))
      (node (ref "P") (pin "MX2") (pinfunction "P1_MX2") (pintype "bidirectional"))
      (node (ref "SEMICOL") (pin "MX2") (pinfunction "P1_MX2") (pintype "bidirectional"))
      (node (ref "U$1") (pin "29") (pinfunction "PB5(ADC12)_29") (pintype "bidirectional"))
    )
    (net (code "14") (name "C11") (class "Default")
      (node (ref "'") (pin "MX2") (pinfunction "P1_MX2") (pintype "bidirectional"))
      (node (ref "-") (pin "MX2") (pinfunction "P1_MX2") (pintype "bidirectional"))
      (node (ref "RSHIFT") (pin "MX2") (pinfunction "P1_MX2") (pintype "bidirectional"))
      (node (ref "U$1") (pin "30") (pinfunction "PB6(ADC13)_30") (pintype "bidirectional"))
      (node (ref "[") (pin "MX2") (pinfunction "P1_MX2") (pintype "bidirectional"))
    )
    (net (code "15") (name "C12") (class "Default")
      (node (ref "=") (pin "MX2") (pinfunction "P1_MX2") (pintype "bidirectional"))
      (node (ref "ENTER") (pin "MX2") (pinfunction "P1_MX2") (pintype "bidirectional"))
      (node (ref "LEFT") (pin "MX2") (pinfunction "P1_MX2") (pintype "bidirectional"))
      (node (ref "U$1") (pin "36") (pinfunction "PF7(ADC7)_36") (pintype "bidirectional"))
      (node (ref "]") (pin "MX2") (pinfunction "P1_MX2") (pintype "bidirectional"))
    )
    (net (code "16") (name "C13") (class "Default")
      (node (ref "BCKSPC") (pin "MX2") (pinfunction "P1_MX2") (pintype "bidirectional"))
      (node (ref "DOWN") (pin "MX2") (pinfunction "P1_MX2") (pintype "bidirectional"))
      (node (ref "U$1") (pin "32") (pinfunction "PC7_32") (pintype "bidirectional"))
      (node (ref "UP") (pin "MX2") (pinfunction "P1_MX2") (pintype "bidirectional"))
      (node (ref "\\") (pin "MX2") (pinfunction "P1_MX2") (pintype "bidirectional"))
    )
    (net (code "17") (name "C14") (class "Default")
      (node (ref "DEL") (pin "MX2") (pinfunction "P1_MX2") (pintype "bidirectional"))
      (node (ref "PAGEDN") (pin "MX2") (pinfunction "P1_MX2") (pintype "bidirectional"))
      (node (ref "PAGEUP") (pin "MX2") (pinfunction "P1_MX2") (pintype "bidirectional"))
      (node (ref "RIGHT") (pin "MX2") (pinfunction "P1_MX2") (pintype "bidirectional"))
      (node (ref "U$1") (pin "31") (pinfunction "PC6_31") (pintype "bidirectional"))
    )
    (net (code "18") (name "D+") (class "Default")
      (node (ref "R3") (pin "2") (pinfunction "2_2") (pintype "passive"))
      (node (ref "U$1") (pin "4") (pinfunction "D+_4") (pintype "bidirectional"))
    )
    (net (code "19") (name "D-") (class "Default")
      (node (ref "R2") (pin "2") (pinfunction "2_2") (pintype "passive"))
      (node (ref "U$1") (pin "3") (pinfunction "D-_3") (pintype "bidirectional"))
    )
    (net (code "20") (name "E1") (class "Default")
      (node (ref "C10") (pin "2") (pinfunction "2_2") (pintype "passive"))
      (node (ref "R7") (pin "2") (pinfunction "2_2") (pintype "passive"))
      (node (ref "U$1") (pin "21") (pinfunction "PD3(TX)_21") (pintype "bidirectional"))
      (node (ref "U1") (pin "E1") (pinfunction "E1_E1") (pintype "bidirectional"))
    )
    (net (code "21") (name "GND") (class "Default")
      (node (ref "C1") (pin "1") (pinfunction "1_1") (pintype "passive"))
      (node (ref "C10") (pin "1") (pinfunction "1_1") (pintype "passive"))
      (node (ref "C11") (pin "1") (pinfunction "1_1") (pintype "passive"))
      (node (ref "C12") (pin "1") (pinfunction "1_1") (pintype "passive"))
      (node (ref "C2") (pin "1") (pinfunction "1_1") (pintype "passive"))
      (node (ref "C3") (pin "1") (pinfunction "1_1") (pintype "passive"))
      (node (ref "C4") (pin "1") (pinfunction "1_1") (pintype "passive"))
      (node (ref "C6") (pin "2") (pinfunction "2_2") (pintype "passive"))
      (node (ref "C7") (pin "2") (pinfunction "2_2") (pintype "passive"))
      (node (ref "C8") (pin "2") (pinfunction "2_2") (pintype "passive"))
      (node (ref "C9") (pin "1") (pinfunction "1_1") (pintype "passive"))
      (node (ref "J1") (pin "4") (pinfunction "4_4") (pintype "bidirectional"))
      (node (ref "J1") (pin "5") (pinfunction "5_5") (pintype "bidirectional"))
      (node (ref "J1") (pin "6") (pinfunction "6_6") (pintype "bidirectional"))
      (node (ref "R1") (pin "1") (pinfunction "1_1") (pintype "passive"))
      (node (ref "S1") (pin "A1") (pinfunction "NO_1_A1") (pintype "bidirectional"))
      (node (ref "S1") (pin "A2") (pinfunction "NO_2_A2") (pintype "bidirectional"))
      (node (ref "U$1") (pin "15") (pinfunction "GND_15") (pintype "bidirectional"))
      (node (ref "U$1") (pin "23") (pinfunction "GND_23") (pintype "bidirectional"))
      (node (ref "U$1") (pin "35") (pinfunction "GND_35") (pintype "bidirectional"))
      (node (ref "U$1") (pin "43") (pinfunction "GND_43") (pintype "bidirectional"))
      (node (ref "U$1") (pin "5") (pinfunction "UGND_5") (pintype "bidirectional"))
      (node (ref "U1") (pin "C1") (pinfunction "C1_C1") (pintype "bidirectional"))
      (node (ref "U1") (pin "D1") (pinfunction "D1_D1") (pintype "bidirectional"))
      (node (ref "Y2") (pin "2") (pinfunction "NC_1_2") (pintype "bidirectional"))
      (node (ref "Y2") (pin "4") (pinfunction "NC_2_4") (pintype "bidirectional"))
    )
    (net (code "22") (name "Net-('-P0)") (class "Default")
      (node (ref "'") (pin "MX1") (pinfunction "P0_MX1") (pintype "bidirectional"))
      (node (ref "D41") (pin "A") (pinfunction "A_A") (pintype "passive"))
    )
    (net (code "23") (name "Net-(,-P0)") (class "Default")
      (node (ref ",") (pin "MX1") (pinfunction "P0_MX1") (pintype "bidirectional"))
      (node (ref "D52") (pin "A") (pinfunction "A_A") (pintype "passive"))
    )
    (net (code "24") (name "Net-(--P0)") (class "Default")
      (node (ref "-") (pin "MX1") (pinfunction "P0_MX1") (pintype "bidirectional"))
      (node (ref "D12") (pin "A") (pinfunction "A_A") (pintype "passive"))
    )
    (net (code "25") (name "Net-(.-P0)") (class "Default")
      (node (ref ".") (pin "MX1") (pinfunction "P0_MX1") (pintype "bidirectional"))
      (node (ref "D53") (pin "A") (pinfunction "A_A") (pintype "passive"))
    )
    (net (code "26") (name "Net-(/-P0)") (class "Default")
      (node (ref "/") (pin "MX1") (pinfunction "P0_MX1") (pintype "bidirectional"))
      (node (ref "D54") (pin "A") (pinfunction "A_A") (pintype "passive"))
    )
    (net (code "27") (name "Net-(0-P0)") (class "Default")
      (node (ref "0") (pin "MX1") (pinfunction "P0_MX1") (pintype "bidirectional"))
      (node (ref "D11") (pin "A") (pinfunction "A_A") (pintype "passive"))
    )
    (net (code "28") (name "Net-(1-P0)") (class "Default")
      (node (ref "1") (pin "MX1") (pinfunction "P0_MX1") (pintype "bidirectional"))
      (node (ref "D2") (pin "A") (pinfunction "A_A") (pintype "passive"))
    )
    (net (code "29") (name "Net-(2-P0)") (class "Default")
      (node (ref "2") (pin "MX1") (pinfunction "P0_MX1") (pintype "bidirectional"))
      (node (ref "D3") (pin "A") (pinfunction "A_A") (pintype "passive"))
    )
    (net (code "30") (name "Net-(3-P0)") (class "Default")
      (node (ref "3") (pin "MX1") (pinfunction "P0_MX1") (pintype "bidirectional"))
      (node (ref "D4") (pin "A") (pinfunction "A_A") (pintype "passive"))
    )
    (net (code "31") (name "Net-(4-P0)") (class "Default")
      (node (ref "4") (pin "MX1") (pinfunction "P0_MX1") (pintype "bidirectional"))
      (node (ref "D5") (pin "A") (pinfunction "A_A") (pintype "passive"))
    )
    (net (code "32") (name "Net-(5-P0)") (class "Default")
      (node (ref "5") (pin "MX1") (pinfunction "P0_MX1") (pintype "bidirectional"))
      (node (ref "D6") (pin "A") (pinfunction "A_A") (pintype "passive"))
    )
    (net (code "33") (name "Net-(6-P0)") (class "Default")
      (node (ref "6") (pin "MX1") (pinfunction "P0_MX1") (pintype "bidirectional"))
      (node (ref "D7") (pin "A") (pinfunction "A_A") (pintype "passive"))
    )
    (net (code "34") (name "Net-(7-P0)") (class "Default")
      (node (ref "7") (pin "MX1") (pinfunction "P0_MX1") (pintype "bidirectional"))
      (node (ref "D8") (pin "A") (pinfunction "A_A") (pintype "passive"))
    )
    (net (code "35") (name "Net-(8-P0)") (class "Default")
      (node (ref "8") (pin "MX1") (pinfunction "P0_MX1") (pintype "bidirectional"))
      (node (ref "D9") (pin "A") (pinfunction "A_A") (pintype "passive"))
    )
    (net (code "36") (name "Net-(9-P0)") (class "Default")
      (node (ref "9") (pin "MX1") (pinfunction "P0_MX1") (pintype "bidirectional"))
      (node (ref "D10") (pin "A") (pinfunction "A_A") (pintype "passive"))
    )
    (net (code "37") (name "Net-(=-P0)") (class "Default")
      (node (ref "=") (pin "MX1") (pinfunction "P0_MX1") (pintype "bidirectional"))
      (node (ref "D13") (pin "A") (pinfunction "A_A") (pintype "passive"))
    )
    (net (code "38") (name "Net-(A-P0)") (class "Default")
      (node (ref "A") (pin "MX1") (pinfunction "P0_MX1") (pintype "bidirectional"))
      (node (ref "D31") (pin "A") (pinfunction "A_A") (pintype "passive"))
    )
    (net (code "39") (name "Net-(ALT-P0)") (class "Default")
      (node (ref "ALT") (pin "MX1") (pinfunction "P0_MX1") (pintype "bidirectional"))
      (node (ref "D59") (pin "A") (pinfunction "A_A") (pintype "passive"))
    )
    (net (code "40") (name "Net-(B-P0)") (class "Default")
      (node (ref "B") (pin "MX1") (pinfunction "P0_MX1") (pintype "bidirectional"))
      (node (ref "D49") (pin "A") (pinfunction "A_A") (pintype "passive"))
    )
    (net (code "41") (name "Net-(BCKSPC-P0)") (class "Default")
      (node (ref "BCKSPC") (pin "MX1") (pinfunction "P0_MX1") (pintype "bidirectional"))
      (node (ref "D14") (pin "A") (pinfunction "A_A") (pintype "passive"))
    )
    (net (code "42") (name "Net-(C-P0)") (class "Default")
      (node (ref "C") (pin "MX1") (pinfunction "P0_MX1") (pintype "bidirectional"))
      (node (ref "D47") (pin "A") (pinfunction "A_A") (pintype "passive"))
    )
    (net (code "43") (name "Net-(CAPS-P0)") (class "Default")
      (node (ref "CAPS") (pin "MX1") (pinfunction "P0_MX1") (pintype "bidirectional"))
      (node (ref "D30") (pin "A") (pinfunction "A_A") (pintype "passive"))
    )
    (net (code "44") (name "Net-(D-P0)") (class "Default")
      (node (ref "D") (pin "MX1") (pinfunction "P0_MX1") (pintype "bidirectional"))
      (node (ref "D33") (pin "A") (pinfunction "A_A") (pintype "passive"))
    )
    (net (code "45") (name "Net-(DEL-P0)") (class "Default")
      (node (ref "D29") (pin "A") (pinfunction "A_A") (pintype "passive"))
      (node (ref "DEL") (pin "MX1") (pinfunction "P0_MX1") (pintype "bidirectional"))
    )
    (net (code "46") (name "Net-(DOWN-P0)") (class "Default")
      (node (ref "D70") (pin "A") (pinfunction "A_A") (pintype "passive"))
      (node (ref "DOWN") (pin "MX1") (pinfunction "P0_MX1") (pintype "bidirectional"))
    )
    (net (code "47") (name "Net-(E-P0)") (class "Default")
      (node (ref "D18") (pin "A") (pinfunction "A_A") (pintype "passive"))
      (node (ref "E") (pin "MX1") (pinfunction "P0_MX1") (pintype "bidirectional"))
    )
    (net (code "48") (name "Net-(ENTER-P0)") (class "Default")
      (node (ref "D42") (pin "A") (pinfunction "A_A") (pintype "passive"))
      (node (ref "ENTER") (pin "MX1") (pinfunction "P0_MX1") (pintype "bidirectional"))
    )
    (net (code "49") (name "Net-(ESC-P0)") (class "Default")
      (node (ref "D1") (pin "A") (pinfunction "A_A") (pintype "passive"))
      (node (ref "ESC") (pin "MX1") (pinfunction "P0_MX1") (pintype "bidirectional"))
    )
    (net (code "50") (name "Net-(F-P0)") (class "Default")
      (node (ref "D34") (pin "A") (pinfunction "A_A") (pintype "passive"))
      (node (ref "F") (pin "MX1") (pinfunction "P0_MX1") (pintype "bidirectional"))
    )
    (net (code "51") (name "Net-(FN-P0)") (class "Default")
      (node (ref "D67") (pin "A") (pinfunction "A_A") (pintype "passive"))
      (node (ref "FN") (pin "MX1") (pinfunction "P0_MX1") (pintype "bidirectional"))
    )
    (net (code "52") (name "Net-(G-P0)") (class "Default")
      (node (ref "D35") (pin "A") (pinfunction "A_A") (pintype "passive"))
      (node (ref "G") (pin "MX1") (pinfunction "P0_MX1") (pintype "bidirectional"))
    )
    (net (code "53") (name "Net-(H-P0)") (class "Default")
      (node (ref "D36") (pin "A") (pinfunction "A_A") (pintype "passive"))
      (node (ref "H") (pin "MX1") (pinfunction "P0_MX1") (pintype "bidirectional"))
    )
    (net (code "54") (name "Net-(I-P0)") (class "Default")
      (node (ref "D23") (pin "A") (pinfunction "A_A") (pintype "passive"))
      (node (ref "I") (pin "MX1") (pinfunction "P0_MX1") (pintype "bidirectional"))
    )
    (net (code "55") (name "Net-(J-P0)") (class "Default")
      (node (ref "D37") (pin "A") (pinfunction "A_A") (pintype "passive"))
      (node (ref "J") (pin "MX1") (pinfunction "P0_MX1") (pintype "bidirectional"))
    )
    (net (code "56") (name "Net-(J1-Pad2)") (class "Default")
      (node (ref "J1") (pin "2") (pinfunction "2_2") (pintype "bidirectional"))
      (node (ref "R2") (pin "1") (pinfunction "1_1") (pintype "passive"))
    )
    (net (code "57") (name "Net-(J1-Pad3)") (class "Default")
      (node (ref "J1") (pin "3") (pinfunction "3_3") (pintype "bidirectional"))
      (node (ref "R3") (pin "1") (pinfunction "1_1") (pintype "passive"))
    )
    (net (code "58") (name "Net-(K-P0)") (class "Default")
      (node (ref "D38") (pin "A") (pinfunction "A_A") (pintype "passive"))
      (node (ref "K") (pin "MX1") (pinfunction "P0_MX1") (pintype "bidirectional"))
    )
    (net (code "59") (name "Net-(L-P0)") (class "Default")
      (node (ref "D39") (pin "A") (pinfunction "A_A") (pintype "passive"))
      (node (ref "L") (pin "MX1") (pinfunction "P0_MX1") (pintype "bidirectional"))
    )
    (net (code "60") (name "Net-(LEFT-P0)") (class "Default")
      (node (ref "D69") (pin "A") (pinfunction "A_A") (pintype "passive"))
      (node (ref "LEFT") (pin "MX1") (pinfunction "P0_MX1") (pintype "bidirectional"))
    )
    (net (code "61") (name "Net-(M-P0)") (class "Default")
      (node (ref "D51") (pin "A") (pinfunction "A_A") (pintype "passive"))
      (node (ref "M") (pin "MX1") (pinfunction "P0_MX1") (pintype "bidirectional"))
    )
    (net (code "62") (name "Net-(N-P0)") (class "Default")
      (node (ref "D50") (pin "A") (pinfunction "A_A") (pintype "passive"))
      (node (ref "N") (pin "MX1") (pinfunction "P0_MX1") (pintype "bidirectional"))
    )
    (net (code "63") (name "Net-(O-P0)") (class "Default")
      (node (ref "D24") (pin "A") (pinfunction "A_A") (pintype "passive"))
      (node (ref "O") (pin "MX1") (pinfunction "P0_MX1") (pintype "bidirectional"))
    )
    (net (code "64") (name "Net-(P-P0)") (class "Default")
      (node (ref "D25") (pin "A") (pinfunction "A_A") (pintype "passive"))
      (node (ref "P") (pin "MX1") (pinfunction "P0_MX1") (pintype "bidirectional"))
    )
    (net (code "65") (name "Net-(PAGEDN-P0)") (class "Default")
      (node (ref "D57") (pin "A") (pinfunction "A_A") (pintype "passive"))
      (node (ref "PAGEDN") (pin "MX1") (pinfunction "P0_MX1") (pintype "bidirectional"))
    )
    (net (code "66") (name "Net-(PAGEUP-P0)") (class "Default")
      (node (ref "D43") (pin "A") (pinfunction "A_A") (pintype "passive"))
      (node (ref "PAGEUP") (pin "MX1") (pinfunction "P0_MX1") (pintype "bidirectional"))
    )
    (net (code "67") (name "Net-(Q-P0)") (class "Default")
      (node (ref "D16") (pin "A") (pinfunction "A_A") (pintype "passive"))
      (node (ref "Q") (pin "MX1") (pinfunction "P0_MX1") (pintype "bidirectional"))
    )
    (net (code "68") (name "Net-(R-P0)") (class "Default")
      (node (ref "D19") (pin "A") (pinfunction "A_A") (pintype "passive"))
      (node (ref "R") (pin "MX1") (pinfunction "P0_MX1") (pintype "bidirectional"))
    )
    (net (code "69") (name "Net-(RALT-P0)") (class "Default")
      (node (ref "D66") (pin "A") (pinfunction "A_A") (pintype "passive"))
      (node (ref "RALT") (pin "MX1") (pinfunction "P0_MX1") (pintype "bidirectional"))
    )
    (net (code "70") (name "Net-(RIGHT-P0)") (class "Default")
      (node (ref "D71") (pin "A") (pinfunction "A_A") (pintype "passive"))
      (node (ref "RIGHT") (pin "MX1") (pinfunction "P0_MX1") (pintype "bidirectional"))
    )
    (net (code "71") (name "Net-(RSHIFT-P0)") (class "Default")
      (node (ref "D55") (pin "A") (pinfunction "A_A") (pintype "passive"))
      (node (ref "RSHIFT") (pin "MX1") (pinfunction "P0_MX1") (pintype "bidirectional"))
    )
    (net (code "72") (name "Net-(S-P0)") (class "Default")
      (node (ref "D32") (pin "A") (pinfunction "A_A") (pintype "passive"))
      (node (ref "S") (pin "MX1") (pinfunction "P0_MX1") (pintype "bidirectional"))
    )
    (net (code "73") (name "Net-(S1-COM_1)") (class "Default")
      (node (ref "R4") (pin "1") (pinfunction "1_1") (pintype "passive"))
      (node (ref "S1") (pin "B1") (pinfunction "COM_1_B1") (pintype "bidirectional"))
      (node (ref "S1") (pin "B2") (pinfunction "COM_2_B2") (pintype "bidirectional"))
      (node (ref "U$1") (pin "13") (pinfunction "~{RESET}_13") (pintype "bidirectional"))
    )
    (net (code "74") (name "Net-(SEMICOL-P0)") (class "Default")
      (node (ref "D40") (pin "A") (pinfunction "A_A") (pintype "passive"))
      (node (ref "SEMICOL") (pin "MX1") (pinfunction "P0_MX1") (pintype "bidirectional"))
    )
    (net (code "75") (name "Net-(SHIFT-P0)") (class "Default")
      (node (ref "D44") (pin "A") (pinfunction "A_A") (pintype "passive"))
      (node (ref "SHIFT") (pin "MX1") (pinfunction "P0_MX1") (pintype "bidirectional"))
    )
    (net (code "76") (name "Net-(SPACE-P0)") (class "Default")
      (node (ref "D62") (pin "A") (pinfunction "A_A") (pintype "passive"))
      (node (ref "SPACE") (pin "MX1") (pinfunction "P0_MX1") (pintype "bidirectional"))
    )
    (net (code "77") (name "Net-(T-P0)") (class "Default")
      (node (ref "D20") (pin "A") (pinfunction "A_A") (pintype "passive"))
      (node (ref "T") (pin "MX1") (pinfunction "P0_MX1") (pintype "bidirectional"))
    )
    (net (code "78") (name "Net-(TAB-P0)") (class "Default")
      (node (ref "D15") (pin "A") (pinfunction "A_A") (pintype "passive"))
      (node (ref "TAB") (pin "MX1") (pinfunction "P0_MX1") (pintype "bidirectional"))
    )
    (net (code "79") (name "Net-(U$1-PE2{slash}~{HWB})") (class "Default")
      (node (ref "R1") (pin "2") (pinfunction "2_2") (pintype "passive"))
      (node (ref "U$1") (pin "33") (pinfunction "PE2/~{HWB}_33") (pintype "bidirectional"))
    )
    (net (code "80") (name "Net-(U$1-UCAP)") (class "Default")
      (node (ref "C1") (pin "2") (pinfunction "2_2") (pintype "passive"))
      (node (ref "U$1") (pin "6") (pinfunction "UCAP_6") (pintype "bidirectional"))
    )
    (net (code "81") (name "Net-(U$1-XTAL1)") (class "Default")
      (node (ref "C6") (pin "1") (pinfunction "1_1") (pintype "passive"))
      (node (ref "U$1") (pin "17") (pinfunction "XTAL1_17") (pintype "bidirectional"))
      (node (ref "Y2") (pin "1") (pinfunction "CRYSTAL_1") (pintype "bidirectional"))
    )
    (net (code "82") (name "Net-(U$1-XTAL2)") (class "Default")
      (node (ref "C7") (pin "1") (pinfunction "1_1") (pintype "passive"))
      (node (ref "U$1") (pin "16") (pinfunction "XTAL2_16") (pintype "bidirectional"))
      (node (ref "Y2") (pin "3") (pinfunction "CRYSTAL__3") (pintype "bidirectional"))
    )
    (net (code "83") (name "Net-(U-P0)") (class "Default")
      (node (ref "D22") (pin "A") (pinfunction "A_A") (pintype "passive"))
      (node (ref "U") (pin "MX1") (pinfunction "P0_MX1") (pintype "bidirectional"))
    )
    (net (code "84") (name "Net-(UP-P0)") (class "Default")
      (node (ref "D56") (pin "A") (pinfunction "A_A") (pintype "passive"))
      (node (ref "UP") (pin "MX1") (pinfunction "P0_MX1") (pintype "bidirectional"))
    )
    (net (code "85") (name "Net-(V-P0)") (class "Default")
      (node (ref "D48") (pin "A") (pinfunction "A_A") (pintype "passive"))
      (node (ref "V") (pin "MX1") (pinfunction "P0_MX1") (pintype "bidirectional"))
    )
    (net (code "86") (name "Net-(W-P0)") (class "Default")
      (node (ref "D17") (pin "A") (pinfunction "A_A") (pintype "passive"))
      (node (ref "W") (pin "MX1") (pinfunction "P0_MX1") (pintype "bidirectional"))
    )
    (net (code "87") (name "Net-(WIN-P0)") (class "Default")
      (node (ref "D58") (pin "A") (pinfunction "A_A") (pintype "passive"))
      (node (ref "WIN") (pin "MX1") (pinfunction "P0_MX1") (pintype "bidirectional"))
    )
    (net (code "88") (name "Net-(X-P0)") (class "Default")
      (node (ref "D46") (pin "A") (pinfunction "A_A") (pintype "passive"))
      (node (ref "X") (pin "MX1") (pinfunction "P0_MX1") (pintype "bidirectional"))
    )
    (net (code "89") (name "Net-(Y-P0)") (class "Default")
      (node (ref "D21") (pin "A") (pinfunction "A_A") (pintype "passive"))
      (node (ref "Y") (pin "MX1") (pinfunction "P0_MX1") (pintype "bidirectional"))
    )
    (net (code "90") (name "Net-(Z-P0)") (class "Default")
      (node (ref "D45") (pin "A") (pinfunction "A_A") (pintype "passive"))
      (node (ref "Z") (pin "MX1") (pinfunction "P0_MX1") (pintype "bidirectional"))
    )
    (net (code "91") (name "Net-([-P0)") (class "Default")
      (node (ref "D26") (pin "A") (pinfunction "A_A") (pintype "passive"))
      (node (ref "[") (pin "MX1") (pinfunction "P0_MX1") (pintype "bidirectional"))
    )
    (net (code "92") (name "Net-(\\-P0)") (class "Default")
      (node (ref "D28") (pin "A") (pinfunction "A_A") (pintype "passive"))
      (node (ref "\\") (pin "MX1") (pinfunction "P0_MX1") (pintype "bidirectional"))
    )
    (net (code "93") (name "Net-(]-P0)") (class "Default")
      (node (ref "D27") (pin "A") (pinfunction "A_A") (pintype "passive"))
      (node (ref "]") (pin "MX1") (pinfunction "P0_MX1") (pintype "bidirectional"))
    )
    (net (code "94") (name "R0") (class "Default")
      (node (ref "D1") (pin "C") (pinfunction "C_C") (pintype "passive"))
      (node (ref "D10") (pin "C") (pinfunction "C_C") (pintype "passive"))
      (node (ref "D11") (pin "C") (pinfunction "C_C") (pintype "passive"))
      (node (ref "D12") (pin "C") (pinfunction "C_C") (pintype "passive"))
      (node (ref "D13") (pin "C") (pinfunction "C_C") (pintype "passive"))
      (node (ref "D14") (pin "C") (pinfunction "C_C") (pintype "passive"))
      (node (ref "D2") (pin "C") (pinfunction "C_C") (pintype "passive"))
      (node (ref "D3") (pin "C") (pinfunction "C_C") (pintype "passive"))
      (node (ref "D4") (pin "C") (pinfunction "C_C") (pintype "passive"))
      (node (ref "D5") (pin "C") (pinfunction "C_C") (pintype "passive"))
      (node (ref "D6") (pin "C") (pinfunction "C_C") (pintype "passive"))
      (node (ref "D7") (pin "C") (pinfunction "C_C") (pintype "passive"))
      (node (ref "D8") (pin "C") (pinfunction "C_C") (pintype "passive"))
      (node (ref "D9") (pin "C") (pinfunction "C_C") (pintype "passive"))
      (node (ref "U$1") (pin "40") (pinfunction "PF1(ADC1)_40") (pintype "bidirectional"))
    )
    (net (code "95") (name "R1") (class "Default")
      (node (ref "D15") (pin "C") (pinfunction "C_C") (pintype "passive"))
      (node (ref "D16") (pin "C") (pinfunction "C_C") (pintype "passive"))
      (node (ref "D17") (pin "C") (pinfunction "C_C") (pintype "passive"))
      (node (ref "D18") (pin "C") (pinfunction "C_C") (pintype "passive"))
      (node (ref "D19") (pin "C") (pinfunction "C_C") (pintype "passive"))
      (node (ref "D20") (pin "C") (pinfunction "C_C") (pintype "passive"))
      (node (ref "D21") (pin "C") (pinfunction "C_C") (pintype "passive"))
      (node (ref "D22") (pin "C") (pinfunction "C_C") (pintype "passive"))
      (node (ref "D23") (pin "C") (pinfunction "C_C") (pintype "passive"))
      (node (ref "D24") (pin "C") (pinfunction "C_C") (pintype "passive"))
      (node (ref "D25") (pin "C") (pinfunction "C_C") (pintype "passive"))
      (node (ref "D26") (pin "C") (pinfunction "C_C") (pintype "passive"))
      (node (ref "D27") (pin "C") (pinfunction "C_C") (pintype "passive"))
      (node (ref "D28") (pin "C") (pinfunction "C_C") (pintype "passive"))
      (node (ref "D29") (pin "C") (pinfunction "C_C") (pintype "passive"))
      (node (ref "U$1") (pin "41") (pinfunction "PF0(ADC0)_41") (pintype "bidirectional"))
    )
    (net (code "96") (name "R2") (class "Default")
      (node (ref "D30") (pin "C") (pinfunction "C_C") (pintype "passive"))
      (node (ref "D31") (pin "C") (pinfunction "C_C") (pintype "passive"))
      (node (ref "D32") (pin "C") (pinfunction "C_C") (pintype "passive"))
      (node (ref "D33") (pin "C") (pinfunction "C_C") (pintype "passive"))
      (node (ref "D34") (pin "C") (pinfunction "C_C") (pintype "passive"))
      (node (ref "D35") (pin "C") (pinfunction "C_C") (pintype "passive"))
      (node (ref "D36") (pin "C") (pinfunction "C_C") (pintype "passive"))
      (node (ref "D37") (pin "C") (pinfunction "C_C") (pintype "passive"))
      (node (ref "D38") (pin "C") (pinfunction "C_C") (pintype "passive"))
      (node (ref "D39") (pin "C") (pinfunction "C_C") (pintype "passive"))
      (node (ref "D40") (pin "C") (pinfunction "C_C") (pintype "passive"))
      (node (ref "D41") (pin "C") (pinfunction "C_C") (pintype "passive"))
      (node (ref "D42") (pin "C") (pinfunction "C_C") (pintype "passive"))
      (node (ref "D43") (pin "C") (pinfunction "C_C") (pintype "passive"))
      (node (ref "U$1") (pin "1") (pinfunction "PE6_1") (pintype "bidirectional"))
    )
    (net (code "97") (name "R3") (class "Default")
      (node (ref "D44") (pin "C") (pinfunction "C_C") (pintype "passive"))
      (node (ref "D45") (pin "C") (pinfunction "C_C") (pintype "passive"))
      (node (ref "D46") (pin "C") (pinfunction "C_C") (pintype "passive"))
      (node (ref "D47") (pin "C") (pinfunction "C_C") (pintype "passive"))
      (node (ref "D48") (pin "C") (pinfunction "C_C") (pintype "passive"))
      (node (ref "D49") (pin "C") (pinfunction "C_C") (pintype "passive"))
      (node (ref "D50") (pin "C") (pinfunction "C_C") (pintype "passive"))
      (node (ref "D51") (pin "C") (pinfunction "C_C") (pintype "passive"))
      (node (ref "D52") (pin "C") (pinfunction "C_C") (pintype "passive"))
      (node (ref "D53") (pin "C") (pinfunction "C_C") (pintype "passive"))
      (node (ref "D54") (pin "C") (pinfunction "C_C") (pintype "passive"))
      (node (ref "D55") (pin "C") (pinfunction "C_C") (pintype "passive"))
      (node (ref "D56") (pin "C") (pinfunction "C_C") (pintype "passive"))
      (node (ref "D57") (pin "C") (pinfunction "C_C") (pintype "passive"))
      (node (ref "U$1") (pin "11") (pinfunction "PB3(MISO)_11") (pintype "bidirectional"))
    )
    (net (code "98") (name "R4") (class "Default")
      (node (ref "D58") (pin "C") (pinfunction "C_C") (pintype "passive"))
      (node (ref "D59") (pin "C") (pinfunction "C_C") (pintype "passive"))
      (node (ref "D62") (pin "C") (pinfunction "C_C") (pintype "passive"))
      (node (ref "D66") (pin "C") (pinfunction "C_C") (pintype "passive"))
      (node (ref "D67") (pin "C") (pinfunction "C_C") (pintype "passive"))
      (node (ref "D69") (pin "C") (pinfunction "C_C") (pintype "passive"))
      (node (ref "D70") (pin "C") (pinfunction "C_C") (pintype "passive"))
      (node (ref "D71") (pin "C") (pinfunction "C_C") (pintype "passive"))
      (node (ref "U$1") (pin "39") (pinfunction "PF4(ADC4)_39") (pintype "bidirectional"))
    )
    (net (code "99") (name "VCC") (class "Default")
      (node (ref "C11") (pin "2") (pinfunction "2_2") (pintype "passive"))
      (node (ref "C12") (pin "2") (pinfunction "2_2") (pintype "passive"))
      (node (ref "C2") (pin "2") (pinfunction "2_2") (pintype "passive"))
      (node (ref "C3") (pin "2") (pinfunction "2_2") (pintype "passive"))
      (node (ref "C4") (pin "2") (pinfunction "2_2") (pintype "passive"))
      (node (ref "J1") (pin "1") (pinfunction "1_1") (pintype "bidirectional"))
      (node (ref "R4") (pin "2") (pinfunction "2_2") (pintype "passive"))
      (node (ref "R5") (pin "2") (pinfunction "2_2") (pintype "passive"))
      (node (ref "R6") (pin "1") (pinfunction "1_1") (pintype "passive"))
      (node (ref "R7") (pin "1") (pinfunction "1_1") (pintype "passive"))
      (node (ref "U$1") (pin "14") (pinfunction "VCC_14") (pintype "bidirectional"))
      (node (ref "U$1") (pin "2") (pinfunction "UVCC_2") (pintype "bidirectional"))
      (node (ref "U$1") (pin "24") (pinfunction "AVCC_24") (pintype "bidirectional"))
      (node (ref "U$1") (pin "34") (pinfunction "VCC_34") (pintype "bidirectional"))
      (node (ref "U$1") (pin "44") (pinfunction "AVCC_44") (pintype "bidirectional"))
      (node (ref "U$1") (pin "7") (pinfunction "VBUS_7") (pintype "bidirectional"))
    )
    (net (code "100") (name "unconnected-(U$1-AREF-Pad42)") (class "Default")
      (node (ref "U$1") (pin "42") (pinfunction "AREF_42") (pintype "bidirectional"))
    )
    (net (code "101") (name "unconnected-(U$1-PF5(ADC5)-Pad38)") (class "Default")
      (node (ref "U$1") (pin "38") (pinfunction "PF5(ADC5)_38") (pintype "bidirectional"))
    )
    (net (code "102") (name "unconnected-(U$1-PF6(ADC6)-Pad37)") (class "Default")
      (node (ref "U$1") (pin "37") (pinfunction "PF6(ADC6)_37") (pintype "bidirectional"))
    )
    (net (code "103") (name "unconnected-(U1-PadMH1)") (class "Default")
      (node (ref "U1") (pin "MH1") (pinfunction "MH1_MH1") (pintype "bidirectional"))
    )
    (net (code "104") (name "unconnected-(U1-PadMH2)") (class "Default")
      (node (ref "U1") (pin "MH2") (pinfunction "MH2_MH2") (pintype "bidirectional"))
    )
  )
)
